# TPS630701_-_Buck_Boost_5V_regulator_brea.net
KiCad netlist of a schematic drawn in EAGLE
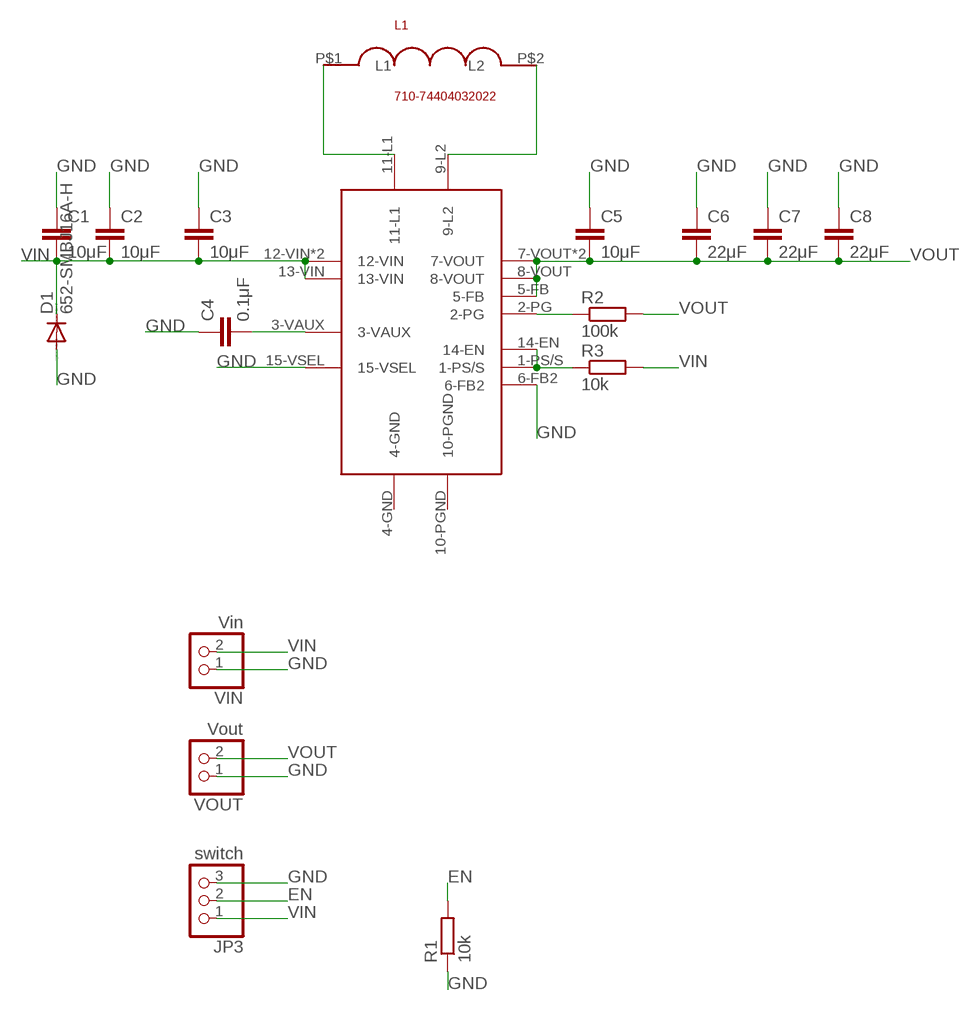
[diagram p0: schematic, sheet 1]

(export (version "E")
  (design (tool "Eeschema 10.0.6"))
  (components
    (comp (ref "C1")
      (value "10μF")
      (footprint "eagle-import:C0805")
      (libsource (lib "eagle-import") (part "C-EUC0805"))
    )
    (comp (ref "C2")
      (value "10μF")
      (footprint "eagle-import:C0805")
      (libsource (lib "eagle-import") (part "C-EUC0805"))
    )
    (comp (ref "C3")
      (value "10μF")
      (footprint "eagle-import:C0603")
      (libsource (lib "eagle-import") (part "C-EUC0603"))
    )
    (comp (ref "C4")
      (value "0.1μF")
      (footprint "eagle-import:C0805")
      (libsource (lib "eagle-import") (part "C-EUC0805"))
    )
    (comp (ref "C5")
      (value "10μF")
      (footprint "eagle-import:C0603")
      (libsource (lib "eagle-import") (part "C-EUC0603"))
    )
    (comp (ref "C6")
      (value "22μF")
      (footprint "eagle-import:C0805")
      (libsource (lib "eagle-import") (part "C-EUC0805"))
    )
    (comp (ref "C7")
      (value "22μF")
      (footprint "eagle-import:C0805")
      (libsource (lib "eagle-import") (part "C-EUC0805"))
    )
    (comp (ref "C8")
      (value "22μF")
      (footprint "eagle-import:C0805")
      (libsource (lib "eagle-import") (part "C-EUC0805"))
    )
    (comp (ref "D1")
      (value "652-SMBJ16A-H")
      (footprint "eagle-import:DO214AA")
      (libsource (lib "eagle-import") (part "DIODE-DO214AA"))
    )
    (comp (ref "IC1")
      (value "TPS630701RNMT")
      (footprint "eagle-import:VQFN")
      (libsource (lib "eagle-import") (part "TPS630701"))
    )
    (comp (ref "JP3")
      (value "switch")
      (footprint "eagle-import:1X03")
      (libsource (lib "eagle-import") (part "PINHD-1X3"))
    )
    (comp (ref "L1")
      (value "710-74404032022")
      (footprint "eagle-import:FFF")
      (libsource (lib "eagle-import") (part "DJNR3015-1R5"))
    )
    (comp (ref "R1")
      (value "10k")
      (footprint "eagle-import:R0805")
      (libsource (lib "eagle-import") (part "R-EU_R0805"))
    )
    (comp (ref "R2")
      (value "100k")
      (footprint "eagle-import:R0805")
      (libsource (lib "eagle-import") (part "R-EU_R0805"))
    )
    (comp (ref "R3")
      (value "10k")
      (footprint "eagle-import:R0805")
      (libsource (lib "eagle-import") (part "R-EU_R0805"))
    )
    (comp (ref "VIN")
      (value "Vin")
      (footprint "eagle-import:1X02")
      (libsource (lib "eagle-import") (part "PINHD-1X2"))
    )
    (comp (ref "VOUT")
      (value "Vout")
      (footprint "eagle-import:1X02")
      (libsource (lib "eagle-import") (part "PINHD-1X2"))
    )
  )
  (nets
    (net (code "1") (name "/EN") (class "Default")
      (node (ref "JP3") (pin "2") (pinfunction "2_2") (pintype "passive"))
      (node (ref "R1") (pin "2") (pinfunction "2_2") (pintype "passive"))
    )
    (net (code "2") (name "/GND") (class "Default")
      (node (ref "C1") (pin "1") (pinfunction "1_1") (pintype "passive"))
      (node (ref "C2") (pin "1") (pinfunction "1_1") (pintype "passive"))
      (node (ref "C3") (pin "1") (pinfunction "1_1") (pintype "passive"))
      (node (ref "C4") (pin "1") (pinfunction "1_1") (pintype "passive"))
      (node (ref "C5") (pin "1") (pinfunction "1_1") (pintype "passive"))
      (node (ref "C6") (pin "1") (pinfunction "1_1") (pintype "passive"))
      (node (ref "C7") (pin "1") (pinfunction "1_1") (pintype "passive"))
      (node (ref "C8") (pin "1") (pinfunction "1_1") (pintype "passive"))
      (node (ref "D1") (pin "A") (pinfunction "A_A") (pintype "passive"))
      (node (ref "IC1") (pin "15-VSEL") (pinfunction "15-VSEL_15-VSEL") (pintype "bidirectional"))
      (node (ref "IC1") (pin "6-FB2") (pinfunction "6-FB2_6-FB2") (pintype "bidirectional"))
      (node (ref "JP3") (pin "3") (pinfunction "3_3") (pintype "passive"))
      (node (ref "R1") (pin "1") (pinfunction "1_1") (pintype "passive"))
      (node (ref "VIN") (pin "1") (pinfunction "1_1") (pintype "passive"))
      (node (ref "VOUT") (pin "1") (pinfunction "1_1") (pintype "passive"))
    )
    (net (code "3") (name "/VIN") (class "Default")
      (node (ref "C1") (pin "2") (pinfunction "2_2") (pintype "passive"))
      (node (ref "C2") (pin "2") (pinfunction "2_2") (pintype "passive"))
      (node (ref "C3") (pin "2") (pinfunction "2_2") (pintype "passive"))
      (node (ref "D1") (pin "C") (pinfunction "C_C") (pintype "passive"))
      (node (ref "IC1") (pin "12-VIN") (pinfunction "12-VIN_12-VIN") (pintype "bidirectional"))
      (node (ref "IC1") (pin "13-VIN") (pinfunction "13-VIN_13-VIN") (pintype "bidirectional"))
      (node (ref "IC1") (pin "VIN") (pinfunction "12-VIN_VIN") (pintype "bidirectional"))
      (node (ref "JP3") (pin "1") (pinfunction "1_1") (pintype "passive"))
      (node (ref "R3") (pin "2") (pinfunction "2_2") (pintype "passive"))
      (node (ref "VIN") (pin "2") (pinfunction "2_2") (pintype "passive"))
    )
    (net (code "4") (name "/VOUT") (class "Default")
      (node (ref "C5") (pin "2") (pinfunction "2_2") (pintype "passive"))
      (node (ref "C6") (pin "2") (pinfunction "2_2") (pintype "passive"))
      (node (ref "C7") (pin "2") (pinfunction "2_2") (pintype "passive"))
      (node (ref "C8") (pin "2") (pinfunction "2_2") (pintype "passive"))
      (node (ref "IC1") (pin "5-FB") (pinfunction "5-FB_5-FB") (pintype "bidirectional"))
      (node (ref "IC1") (pin "7-VOUT") (pinfunction "7-VOUT_7-VOUT") (pintype "bidirectional"))
      (node (ref "IC1") (pin "8-VOUT") (pinfunction "8-VOUT_8-VOUT") (pintype "bidirectional"))
      (node (ref "IC1") (pin "VOUT") (pinfunction "7-VOUT_VOUT") (pintype "bidirectional"))
      (node (ref "R2") (pin "2") (pinfunction "2_2") (pintype "passive"))
      (node (ref "VOUT") (pin "2") (pinfunction "2_2") (pintype "passive"))
    )
    (net (code "5") (name "Net-(C4-Pad2)") (class "Default")
      (node (ref "C4") (pin "2") (pinfunction "2_2") (pintype "passive"))
      (node (ref "IC1") (pin "3-VAUX") (pinfunction "3-VAUX_3-VAUX") (pintype "bidirectional"))
    )
    (net (code "6") (name "Net-(IC1-Pad1-PS{slash}S)") (class "Default")
      (node (ref "IC1") (pin "1-PS/S") (pinfunction "1-PS/S_1-PS/S") (pintype "bidirectional"))
      (node (ref "IC1") (pin "14-EN") (pinfunction "14-EN_14-EN") (pintype "bidirectional"))
      (node (ref "R3") (pin "1") (pinfunction "1_1") (pintype "passive"))
    )
    (net (code "7") (name "Net-(IC1-Pad2-PG)") (class "Default")
      (node (ref "IC1") (pin "2-PG") (pinfunction "2-PG_2-PG") (pintype "bidirectional"))
      (node (ref "R2") (pin "1") (pinfunction "1_1") (pintype "passive"))
    )
    (net (code "8") (name "Net-(L1-L1)") (class "Default")
      (node (ref "IC1") (pin "11-L1") (pinfunction "11-L1_11-L1") (pintype "bidirectional"))
      (node (ref "L1") (pin "P$1") (pinfunction "L1_P$1") (pintype "bidirectional"))
    )
    (net (code "9") (name "Net-(L1-L2)") (class "Default")
      (node (ref "IC1") (pin "9-L2") (pinfunction "9-L2_9-L2") (pintype "bidirectional"))
      (node (ref "L1") (pin "P$2") (pinfunction "L2_P$2") (pintype "bidirectional"))
    )
    (net (code "10") (name "unconnected-(IC1-Pad4-GND)") (class "Default")
      (node (ref "IC1") (pin "4-GND") (pinfunction "4-GND_4-GND") (pintype "bidirectional"))
    )
    (net (code "11") (name "unconnected-(IC1-Pad10-PGND)") (class "Default")
      (node (ref "IC1") (pin "10-PGND") (pinfunction "10-PGND_10-PGND") (pintype "bidirectional"))
    )
  )
)
